# Eye-of-Ord-v1_2.net
KiCad netlist of a schematic drawn in EAGLE
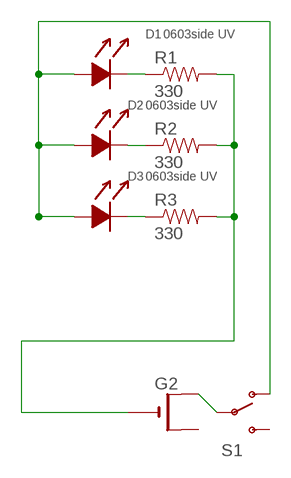
[diagram p0: schematic, sheet 1]

(export (version "E")
  (design (tool "Eeschema 10.0.6"))
  (components
    (comp (ref "D1")
      (value "0603side UV")
      (footprint "eagle-import:SMD-0603-LED-SIDE")
      (libsource (lib "eagle-import") (part "0603SIDELED"))
    )
    (comp (ref "D2")
      (value "0603side UV")
      (footprint "eagle-import:SMD-0603-LED-SIDE")
      (libsource (lib "eagle-import") (part "0603SIDELED"))
    )
    (comp (ref "D3")
      (value "0603side UV")
      (footprint "eagle-import:SMD-0603-LED-SIDE")
      (libsource (lib "eagle-import") (part "0603SIDELED"))
    )
    (comp (ref "G2")
      (value "CR2032SMT")
      (footprint "eagle-import:CR2032-SMD")
      (libsource (lib "eagle-import") (part "CR2032SMT"))
    )
    (comp (ref "R1")
      (value "330")
      (footprint "eagle-import:0603-RES")
      (libsource (lib "eagle-import") (part "RESISTOR0603-RES"))
    )
    (comp (ref "R2")
      (value "330")
      (footprint "eagle-import:0603-RES")
      (libsource (lib "eagle-import") (part "RESISTOR0603-RES"))
    )
    (comp (ref "R3")
      (value "330")
      (footprint "eagle-import:0603-RES")
      (libsource (lib "eagle-import") (part "RESISTOR0603-RES"))
    )
    (comp (ref "S1")
      (value "SWITCH-SPDT-SMD-A")
      (footprint "eagle-import:SWITCH-SPST-SMD-A")
      (libsource (lib "eagle-import") (part "SWITCH-SPDT-SMD-A"))
    )
  )
  (nets
    (net (code "1") (name "Net-(D1-K)") (class "Default")
      (node (ref "D1") (pin "C") (pinfunction "K_C") (pintype "bidirectional"))
      (node (ref "R1") (pin "1") (pinfunction "1_1") (pintype "passive"))
    )
    (net (code "2") (name "Net-(D2-K)") (class "Default")
      (node (ref "D2") (pin "C") (pinfunction "K_C") (pintype "bidirectional"))
      (node (ref "R2") (pin "1") (pinfunction "1_1") (pintype "passive"))
    )
    (net (code "3") (name "Net-(D3-K)") (class "Default")
      (node (ref "D3") (pin "C") (pinfunction "K_C") (pintype "bidirectional"))
      (node (ref "R3") (pin "1") (pinfunction "1_1") (pintype "passive"))
    )
    (net (code "4") (name "Net-(G2-+)") (class "Default")
      (node (ref "G2") (pin "+$1") (pinfunction "+_+$1") (pintype "passive"))
      (node (ref "S1") (pin "2") (pinfunction "P_2") (pintype "passive"))
    )
    (net (code "5") (name "Net-(G2-Pad-)") (class "Default")
      (node (ref "G2") (pin "-") (pinfunction "-_-") (pintype "passive"))
      (node (ref "R1") (pin "2") (pinfunction "2_2") (pintype "passive"))
      (node (ref "R2") (pin "2") (pinfunction "2_2") (pintype "passive"))
      (node (ref "R3") (pin "2") (pinfunction "2_2") (pintype "passive"))
    )
    (net (code "6") (name "Net-(S1-O)") (class "Default")
      (node (ref "D1") (pin "A") (pinfunction "A_A") (pintype "bidirectional"))
      (node (ref "D2") (pin "A") (pinfunction "A_A") (pintype "bidirectional"))
      (node (ref "D3") (pin "A") (pinfunction "A_A") (pintype "bidirectional"))
      (node (ref "S1") (pin "1") (pinfunction "O_1") (pintype "passive"))
    )
    (net (code "7") (name "unconnected-(G2-+1-Pad+$2)") (class "Default")
      (node (ref "G2") (pin "+$2") (pinfunction "+1_+$2") (pintype "passive"))
    )
    (net (code "8") (name "unconnected-(S1-S-Pad3)") (class "Default")
      (node (ref "S1") (pin "3") (pinfunction "S_3") (pintype "passive"))
    )
  )
)
